# wiLED.net
KiCad netlist of a schematic drawn in EAGLE
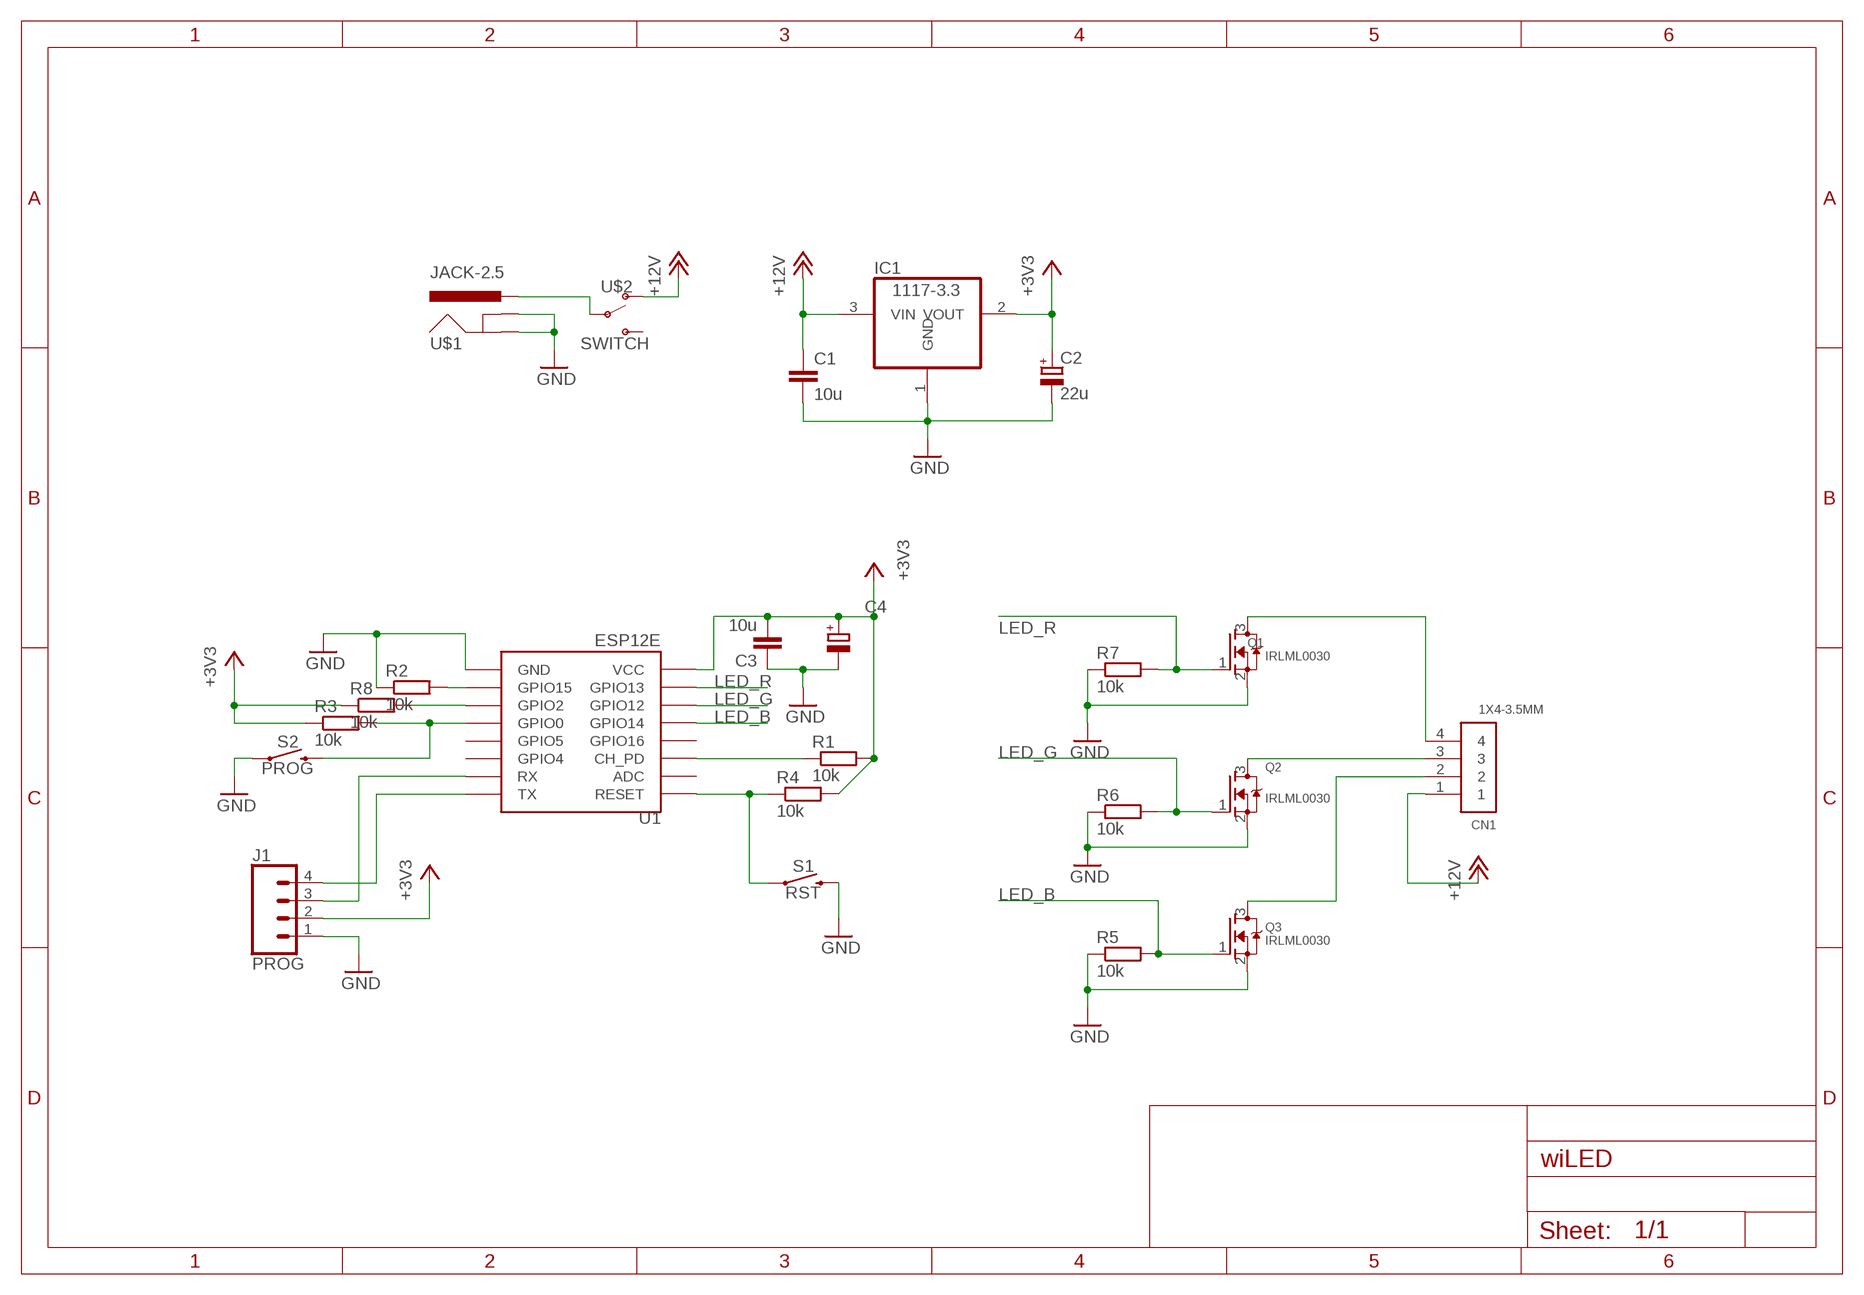
[diagram p0: schematic, sheet 1]

(export (version "E")
  (design (tool "Eeschema 10.0.6"))
  (components
    (comp (ref "C1")
      (value "10u")
      (footprint "eagle-import:C0805")
      (libsource (lib "eagle-import") (part "C-EUC0805"))
    )
    (comp (ref "C2")
      (value "22u")
      (footprint "eagle-import:SMC_A")
      (libsource (lib "eagle-import") (part "CPOL-EUSMCA"))
    )
    (comp (ref "C3")
      (value "10u")
      (footprint "eagle-import:C0805")
      (libsource (lib "eagle-import") (part "C-EUC0805"))
    )
    (comp (ref "C4")
      (value "CPOL-EUSMCC")
      (footprint "eagle-import:SMC_C")
      (libsource (lib "eagle-import") (part "CPOL-EUSMCC"))
    )
    (comp (ref "CN1")
      (value "1X4-3.5MM")
      (footprint "eagle-import:1X04-3.5MM")
      (libsource (lib "eagle-import") (part "1X4-3.5MM"))
    )
    (comp (ref "IC1")
      (value "1117-3.3")
      (footprint "eagle-import:SOT223")
      (fields (field (name "MPN") "REG1117"))
      (libsource (lib "eagle-import") (part "REG1117"))
    )
    (comp (ref "J1")
      (value "PROG")
      (footprint "eagle-import:1X04")
      (libsource (lib "eagle-import") (part "CONN_04"))
    )
    (comp (ref "Q1")
      (value "IRLML0030")
      (footprint "eagle-import:SOT23")
      (libsource (lib "eagle-import") (part "MOSFET-NREFLOW"))
    )
    (comp (ref "Q2")
      (value "IRLML0030")
      (footprint "eagle-import:SOT23")
      (libsource (lib "eagle-import") (part "MOSFET-NREFLOW"))
    )
    (comp (ref "Q3")
      (value "IRLML0030")
      (footprint "eagle-import:SOT23")
      (libsource (lib "eagle-import") (part "MOSFET-NREFLOW"))
    )
    (comp (ref "R1")
      (value "10k")
      (footprint "eagle-import:M0805")
      (libsource (lib "eagle-import") (part "R-EU_M0805"))
    )
    (comp (ref "R2")
      (value "10k")
      (footprint "eagle-import:M0805")
      (libsource (lib "eagle-import") (part "R-EU_M0805"))
    )
    (comp (ref "R3")
      (value "10k")
      (footprint "eagle-import:M0805")
      (libsource (lib "eagle-import") (part "R-EU_M0805"))
    )
    (comp (ref "R4")
      (value "10k")
      (footprint "eagle-import:M0805")
      (libsource (lib "eagle-import") (part "R-EU_M0805"))
    )
    (comp (ref "R5")
      (value "10k")
      (footprint "eagle-import:M0805")
      (libsource (lib "eagle-import") (part "R-EU_M0805"))
    )
    (comp (ref "R6")
      (value "10k")
      (footprint "eagle-import:M0805")
      (libsource (lib "eagle-import") (part "R-EU_M0805"))
    )
    (comp (ref "R7")
      (value "10k")
      (footprint "eagle-import:M0805")
      (libsource (lib "eagle-import") (part "R-EU_M0805"))
    )
    (comp (ref "R8")
      (value "10k")
      (footprint "eagle-import:M0805")
      (libsource (lib "eagle-import") (part "R-EU_M0805"))
    )
    (comp (ref "S1")
      (value "RST")
      (footprint "eagle-import:TACTILE_SWITCH_SMD_6.0X3.5MM")
      (libsource (lib "eagle-import") (part "MOMENTARY-SWITCH-SPST-SMD-6.0X3.5MM"))
    )
    (comp (ref "S2")
      (value "PROG")
      (footprint "eagle-import:TACTILE_SWITCH_SMD_6.0X3.5MM")
      (libsource (lib "eagle-import") (part "MOMENTARY-SWITCH-SPST-SMD-6.0X3.5MM"))
    )
    (comp (ref "U$1")
      (value "JACK-2.5")
      (footprint "eagle-import:DC-2.5")
      (libsource (lib "eagle-import") (part "JACK-2.5"))
    )
    (comp (ref "U$2")
      (value "SWITCH")
      (footprint "eagle-import:SWITCH")
      (libsource (lib "eagle-import") (part "SWITCH"))
    )
    (comp (ref "U1")
      (value "ESP12E")
      (footprint "eagle-import:ESP12-SMD")
      (libsource (lib "eagle-import") (part "ESP12SMD"))
    )
  )
  (nets
    (net (code "1") (name "+3V3") (class "Default")
      (node (ref "C2") (pin "+") (pinfunction "+_+") (pintype "passive"))
      (node (ref "C3") (pin "2") (pinfunction "2_2") (pintype "passive"))
      (node (ref "C4") (pin "+") (pinfunction "+_+") (pintype "passive"))
      (node (ref "IC1") (pin "2") (pinfunction "VOUT_2") (pintype "output"))
      (node (ref "J1") (pin "2") (pinfunction "2_2") (pintype "passive"))
      (node (ref "R1") (pin "2") (pinfunction "2_2") (pintype "passive"))
      (node (ref "R3") (pin "1") (pinfunction "1_1") (pintype "passive"))
      (node (ref "R4") (pin "2") (pinfunction "2_2") (pintype "passive"))
      (node (ref "R8") (pin "1") (pinfunction "1_1") (pintype "passive"))
      (node (ref "U1") (pin "VCC") (pinfunction "VCC_VCC") (pintype "bidirectional"))
    )
    (net (code "2") (name "+12V") (class "Default")
      (node (ref "C1") (pin "1") (pinfunction "1_1") (pintype "passive"))
      (node (ref "CN1") (pin "1") (pinfunction "1_1") (pintype "bidirectional"))
      (node (ref "IC1") (pin "3") (pinfunction "VIN_3") (pintype "input"))
      (node (ref "U$2") (pin "P$1") (pinfunction "O_P$1") (pintype "passive"))
    )
    (net (code "3") (name "/LED_B") (class "Default")
      (node (ref "Q3") (pin "1") (pinfunction "G_1") (pintype "bidirectional"))
      (node (ref "R5") (pin "2") (pinfunction "2_2") (pintype "passive"))
      (node (ref "U1") (pin "GPIO14") (pinfunction "GPIO14_GPIO14") (pintype "bidirectional"))
    )
    (net (code "4") (name "/LED_G") (class "Default")
      (node (ref "Q2") (pin "1") (pinfunction "G_1") (pintype "bidirectional"))
      (node (ref "R6") (pin "2") (pinfunction "2_2") (pintype "passive"))
      (node (ref "U1") (pin "GPIO12") (pinfunction "GPIO12_GPIO12") (pintype "bidirectional"))
    )
    (net (code "5") (name "/LED_R") (class "Default")
      (node (ref "Q1") (pin "1") (pinfunction "G_1") (pintype "bidirectional"))
      (node (ref "R7") (pin "2") (pinfunction "2_2") (pintype "passive"))
      (node (ref "U1") (pin "GPIO13") (pinfunction "GPIO13_GPIO13") (pintype "bidirectional"))
    )
    (net (code "6") (name "GND") (class "Default")
      (node (ref "C1") (pin "2") (pinfunction "2_2") (pintype "passive"))
      (node (ref "C2") (pin "-") (pinfunction "-_-") (pintype "passive"))
      (node (ref "C3") (pin "1") (pinfunction "1_1") (pintype "passive"))
      (node (ref "C4") (pin "-") (pinfunction "-_-") (pintype "passive"))
      (node (ref "IC1") (pin "1") (pinfunction "GND_1") (pintype "power_in"))
      (node (ref "J1") (pin "1") (pinfunction "1_1") (pintype "passive"))
      (node (ref "Q1") (pin "2") (pinfunction "S_2") (pintype "bidirectional"))
      (node (ref "Q2") (pin "2") (pinfunction "S_2") (pintype "bidirectional"))
      (node (ref "Q3") (pin "2") (pinfunction "S_2") (pintype "bidirectional"))
      (node (ref "R2") (pin "1") (pinfunction "1_1") (pintype "passive"))
      (node (ref "R5") (pin "1") (pinfunction "1_1") (pintype "passive"))
      (node (ref "R6") (pin "1") (pinfunction "1_1") (pintype "passive"))
      (node (ref "R7") (pin "1") (pinfunction "1_1") (pintype "passive"))
      (node (ref "S1") (pin "2") (pinfunction "2_2") (pintype "passive"))
      (node (ref "S2") (pin "1") (pinfunction "1_1") (pintype "passive"))
      (node (ref "U$1") (pin "P$1") (pinfunction "GND_P$1") (pintype "bidirectional"))
      (node (ref "U$1") (pin "P$3") (pinfunction "GNDBREAK_P$3") (pintype "bidirectional"))
      (node (ref "U1") (pin "GND") (pinfunction "GND_GND") (pintype "bidirectional"))
    )
    (net (code "7") (name "Net-(Q1-D)") (class "Default")
      (node (ref "CN1") (pin "4") (pinfunction "4_4") (pintype "bidirectional"))
      (node (ref "Q1") (pin "3") (pinfunction "D_3") (pintype "bidirectional"))
    )
    (net (code "8") (name "Net-(Q2-D)") (class "Default")
      (node (ref "CN1") (pin "3") (pinfunction "3_3") (pintype "bidirectional"))
      (node (ref "Q2") (pin "3") (pinfunction "D_3") (pintype "bidirectional"))
    )
    (net (code "9") (name "Net-(Q3-D)") (class "Default")
      (node (ref "CN1") (pin "2") (pinfunction "2_2") (pintype "bidirectional"))
      (node (ref "Q3") (pin "3") (pinfunction "D_3") (pintype "bidirectional"))
    )
    (net (code "10") (name "Net-(R1-Pad1)") (class "Default")
      (node (ref "R1") (pin "1") (pinfunction "1_1") (pintype "passive"))
      (node (ref "U1") (pin "CH_PD") (pinfunction "CH_PD_CH_PD") (pintype "bidirectional"))
    )
    (net (code "11") (name "Net-(R2-Pad2)") (class "Default")
      (node (ref "R2") (pin "2") (pinfunction "2_2") (pintype "passive"))
      (node (ref "U1") (pin "GPIO15") (pinfunction "GPIO15_GPIO15") (pintype "bidirectional"))
    )
    (net (code "12") (name "Net-(R3-Pad2)") (class "Default")
      (node (ref "R3") (pin "2") (pinfunction "2_2") (pintype "passive"))
      (node (ref "S2") (pin "2") (pinfunction "2_2") (pintype "passive"))
      (node (ref "U1") (pin "GPIO0") (pinfunction "GPIO0_GPIO0") (pintype "bidirectional"))
    )
    (net (code "13") (name "Net-(R4-Pad1)") (class "Default")
      (node (ref "R4") (pin "1") (pinfunction "1_1") (pintype "passive"))
      (node (ref "S1") (pin "1") (pinfunction "1_1") (pintype "passive"))
      (node (ref "U1") (pin "RESET") (pinfunction "RESET_RESET") (pintype "bidirectional"))
    )
    (net (code "14") (name "Net-(R8-Pad2)") (class "Default")
      (node (ref "R8") (pin "2") (pinfunction "2_2") (pintype "passive"))
      (node (ref "U1") (pin "GPIO2") (pinfunction "GPIO2_GPIO2") (pintype "bidirectional"))
    )
    (net (code "15") (name "Net-(U$1-PWR)") (class "Default")
      (node (ref "U$1") (pin "P$2") (pinfunction "PWR_P$2") (pintype "bidirectional"))
      (node (ref "U$2") (pin "P$2") (pinfunction "P_P$2") (pintype "passive"))
    )
    (net (code "16") (name "Net-(U1-RX)") (class "Default")
      (node (ref "J1") (pin "3") (pinfunction "3_3") (pintype "passive"))
      (node (ref "U1") (pin "RXD0") (pinfunction "RX_RXD0") (pintype "bidirectional"))
    )
    (net (code "17") (name "Net-(U1-TX)") (class "Default")
      (node (ref "J1") (pin "4") (pinfunction "4_4") (pintype "passive"))
      (node (ref "U1") (pin "TXD0") (pinfunction "TX_TXD0") (pintype "bidirectional"))
    )
    (net (code "18") (name "unconnected-(U$2-S-PadP$3)") (class "Default")
      (node (ref "U$2") (pin "P$3") (pinfunction "S_P$3") (pintype "passive"))
    )
    (net (code "19") (name "unconnected-(U1-PadADC)") (class "Default")
      (node (ref "U1") (pin "ADC") (pinfunction "ADC_ADC") (pintype "bidirectional"))
    )
    (net (code "20") (name "unconnected-(U1-PadGPIO4)") (class "Default")
      (node (ref "U1") (pin "GPIO4") (pinfunction "GPIO4_GPIO4") (pintype "bidirectional"))
    )
    (net (code "21") (name "unconnected-(U1-PadGPIO5)") (class "Default")
      (node (ref "U1") (pin "GPIO5") (pinfunction "GPIO5_GPIO5") (pintype "bidirectional"))
    )
    (net (code "22") (name "unconnected-(U1-PadGPIO16)") (class "Default")
      (node (ref "U1") (pin "GPIO16") (pinfunction "GPIO16_GPIO16") (pintype "bidirectional"))
    )
  )
)
